# olimex_add_on.net
KiCad netlist of a schematic drawn in EAGLE
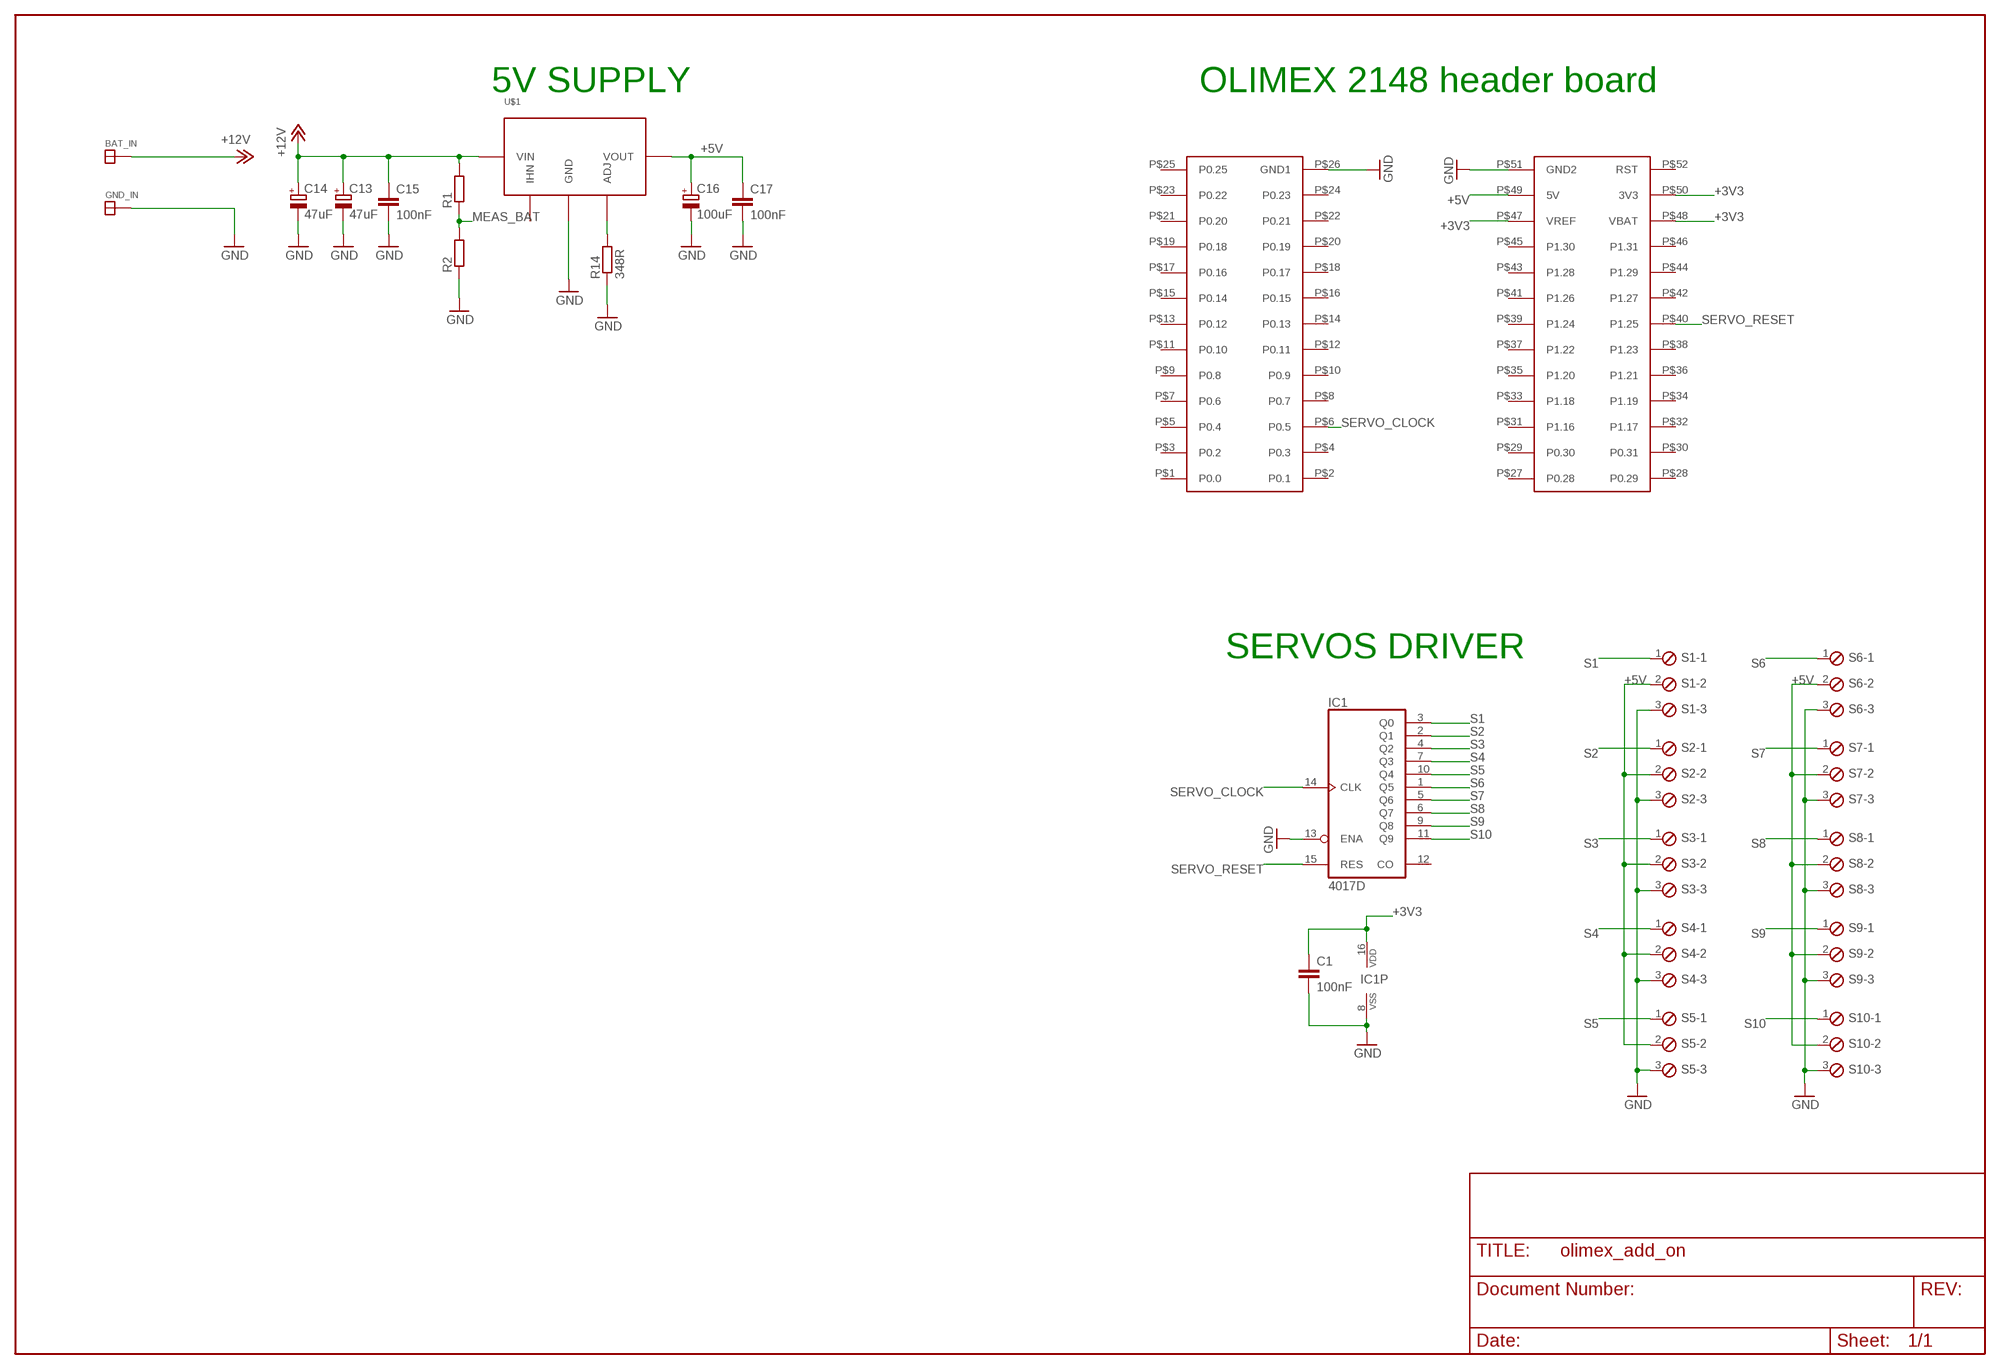
[diagram p0: schematic, sheet 1]

(export (version "E")
  (design (tool "Eeschema 10.0.6"))
  (components
    (comp (ref "BAT_IN")
      (value "SOLDER_PAD150_75")
      (footprint "eagle-import:SOLD_PAD_150_75")
      (libsource (lib "eagle-import") (part "SOLDER_PAD150_75"))
    )
    (comp (ref "C1")
      (value "100nF")
      (footprint "eagle-import:C0805K")
      (libsource (lib "eagle-import") (part "C-EUC0805K"))
    )
    (comp (ref "C13")
      (value "47uF")
      (footprint "eagle-import:SMC_D")
      (libsource (lib "eagle-import") (part "CPOL-EUSMCD"))
    )
    (comp (ref "C14")
      (value "47uF")
      (footprint "eagle-import:SMC_D")
      (libsource (lib "eagle-import") (part "CPOL-EUSMCD"))
    )
    (comp (ref "C15")
      (value "100nF")
      (footprint "eagle-import:C1206K")
      (libsource (lib "eagle-import") (part "C-EUC1206K"))
    )
    (comp (ref "C16")
      (value "100uF")
      (footprint "eagle-import:SMC_D")
      (libsource (lib "eagle-import") (part "CPOL-EUSMCD"))
    )
    (comp (ref "C17")
      (value "100nF")
      (footprint "eagle-import:C1206K")
      (libsource (lib "eagle-import") (part "C-EUC1206K"))
    )
    (comp (ref "GND_IN")
      (value "SOLDER_PAD150_75")
      (footprint "eagle-import:SOLD_PAD_150_75")
      (libsource (lib "eagle-import") (part "SOLDER_PAD150_75"))
    )
    (comp (ref "IC1")
      (value "4017D")
      (footprint "eagle-import:SO16")
      (libsource (lib "eagle-import") (part "4017D"))
    )
    (comp (ref "R1")
      (value "R-EU_R0805")
      (footprint "eagle-import:R0805")
      (libsource (lib "eagle-import") (part "R-EU_R0805"))
    )
    (comp (ref "R2")
      (value "R-EU_R0805")
      (footprint "eagle-import:R0805")
      (libsource (lib "eagle-import") (part "R-EU_R0805"))
    )
    (comp (ref "R14")
      (value "348R")
      (footprint "eagle-import:R0805")
      (libsource (lib "eagle-import") (part "R-EU_R0805"))
    )
    (comp (ref "S1")
      (value "MPT3")
      (footprint "eagle-import:3POL254")
      (libsource (lib "eagle-import") (part "MPT3"))
    )
    (comp (ref "S2")
      (value "MPT3")
      (footprint "eagle-import:3POL254")
      (libsource (lib "eagle-import") (part "MPT3"))
    )
    (comp (ref "S3")
      (value "MPT3")
      (footprint "eagle-import:3POL254")
      (libsource (lib "eagle-import") (part "MPT3"))
    )
    (comp (ref "S4")
      (value "MPT3")
      (footprint "eagle-import:3POL254")
      (libsource (lib "eagle-import") (part "MPT3"))
    )
    (comp (ref "S5")
      (value "MPT3")
      (footprint "eagle-import:3POL254")
      (libsource (lib "eagle-import") (part "MPT3"))
    )
    (comp (ref "S6")
      (value "MPT3")
      (footprint "eagle-import:3POL254")
      (libsource (lib "eagle-import") (part "MPT3"))
    )
    (comp (ref "S7")
      (value "MPT3")
      (footprint "eagle-import:3POL254")
      (libsource (lib "eagle-import") (part "MPT3"))
    )
    (comp (ref "S8")
      (value "MPT3")
      (footprint "eagle-import:3POL254")
      (libsource (lib "eagle-import") (part "MPT3"))
    )
    (comp (ref "S9")
      (value "MPT3")
      (footprint "eagle-import:3POL254")
      (libsource (lib "eagle-import") (part "MPT3"))
    )
    (comp (ref "S10")
      (value "MPT3")
      (footprint "eagle-import:3POL254")
      (libsource (lib "eagle-import") (part "MPT3"))
    )
    (comp (ref "U$1")
      (value "PTH")
      (footprint "eagle-import:PTH")
      (libsource (lib "eagle-import") (part "PTH"))
    )
    (comp (ref "U$5")
      (value "OLIMEX_2148")
      (footprint "eagle-import:OLIMEX_2148")
      (libsource (lib "eagle-import") (part "OLIMEX_2148"))
    )
  )
  (nets
    (net (code "1") (name "+12V") (class "Default")
      (node (ref "BAT_IN") (pin "P$1") (pinfunction "P$1_P$1") (pintype "bidirectional"))
      (node (ref "C13") (pin "+") (pinfunction "+_+") (pintype "passive"))
      (node (ref "C14") (pin "+") (pinfunction "+_+") (pintype "passive"))
      (node (ref "C15") (pin "1") (pinfunction "1_1") (pintype "passive"))
      (node (ref "R1") (pin "2") (pinfunction "2_2") (pintype "passive"))
      (node (ref "U$1") (pin "P$1") (pinfunction "VIN_P$1") (pintype "bidirectional"))
    )
    (net (code "2") (name "/+3V3") (class "Default")
      (node (ref "C1") (pin "1") (pinfunction "1_1") (pintype "passive"))
      (node (ref "IC1") (pin "16") (pinfunction "VDD_16") (pintype "power_in"))
      (node (ref "U$5") (pin "P$47") (pinfunction "VREF_P$47") (pintype "bidirectional"))
      (node (ref "U$5") (pin "P$48") (pinfunction "VBAT_P$48") (pintype "bidirectional"))
      (node (ref "U$5") (pin "P$50") (pinfunction "3V3_P$50") (pintype "bidirectional"))
    )
    (net (code "3") (name "/+5V") (class "Default")
      (node (ref "C16") (pin "+") (pinfunction "+_+") (pintype "passive"))
      (node (ref "C17") (pin "1") (pinfunction "1_1") (pintype "passive"))
      (node (ref "S1") (pin "2") (pinfunction "1_2") (pintype "passive"))
      (node (ref "S10") (pin "2") (pinfunction "1_2") (pintype "passive"))
      (node (ref "S2") (pin "2") (pinfunction "1_2") (pintype "passive"))
      (node (ref "S3") (pin "2") (pinfunction "1_2") (pintype "passive"))
      (node (ref "S4") (pin "2") (pinfunction "1_2") (pintype "passive"))
      (node (ref "S5") (pin "2") (pinfunction "1_2") (pintype "passive"))
      (node (ref "S6") (pin "2") (pinfunction "1_2") (pintype "passive"))
      (node (ref "S7") (pin "2") (pinfunction "1_2") (pintype "passive"))
      (node (ref "S8") (pin "2") (pinfunction "1_2") (pintype "passive"))
      (node (ref "S9") (pin "2") (pinfunction "1_2") (pintype "passive"))
      (node (ref "U$1") (pin "P$3") (pinfunction "VOUT_P$3") (pintype "bidirectional"))
      (node (ref "U$5") (pin "P$49") (pinfunction "5V_P$49") (pintype "bidirectional"))
    )
    (net (code "4") (name "/MEAS_BAT") (class "Default")
      (node (ref "R1") (pin "1") (pinfunction "1_1") (pintype "passive"))
      (node (ref "R2") (pin "2") (pinfunction "2_2") (pintype "passive"))
    )
    (net (code "5") (name "/S1") (class "Default")
      (node (ref "IC1") (pin "3") (pinfunction "Q0_3") (pintype "output"))
      (node (ref "S1") (pin "1") (pinfunction "1_1") (pintype "passive"))
    )
    (net (code "6") (name "/S2") (class "Default")
      (node (ref "IC1") (pin "2") (pinfunction "Q1_2") (pintype "output"))
      (node (ref "S2") (pin "1") (pinfunction "1_1") (pintype "passive"))
    )
    (net (code "7") (name "/S3") (class "Default")
      (node (ref "IC1") (pin "4") (pinfunction "Q2_4") (pintype "output"))
      (node (ref "S3") (pin "1") (pinfunction "1_1") (pintype "passive"))
    )
    (net (code "8") (name "/S4") (class "Default")
      (node (ref "IC1") (pin "7") (pinfunction "Q3_7") (pintype "output"))
      (node (ref "S4") (pin "1") (pinfunction "1_1") (pintype "passive"))
    )
    (net (code "9") (name "/S5") (class "Default")
      (node (ref "IC1") (pin "10") (pinfunction "Q4_10") (pintype "output"))
      (node (ref "S5") (pin "1") (pinfunction "1_1") (pintype "passive"))
    )
    (net (code "10") (name "/S6") (class "Default")
      (node (ref "IC1") (pin "1") (pinfunction "Q5_1") (pintype "output"))
      (node (ref "S6") (pin "1") (pinfunction "1_1") (pintype "passive"))
    )
    (net (code "11") (name "/S7") (class "Default")
      (node (ref "IC1") (pin "5") (pinfunction "Q6_5") (pintype "output"))
      (node (ref "S7") (pin "1") (pinfunction "1_1") (pintype "passive"))
    )
    (net (code "12") (name "/S8") (class "Default")
      (node (ref "IC1") (pin "6") (pinfunction "Q7_6") (pintype "output"))
      (node (ref "S8") (pin "1") (pinfunction "1_1") (pintype "passive"))
    )
    (net (code "13") (name "/S9") (class "Default")
      (node (ref "IC1") (pin "9") (pinfunction "Q8_9") (pintype "output"))
      (node (ref "S9") (pin "1") (pinfunction "1_1") (pintype "passive"))
    )
    (net (code "14") (name "/S10") (class "Default")
      (node (ref "IC1") (pin "11") (pinfunction "Q9_11") (pintype "output"))
      (node (ref "S10") (pin "1") (pinfunction "1_1") (pintype "passive"))
    )
    (net (code "15") (name "/SERVO_CLOCK") (class "Default")
      (node (ref "IC1") (pin "14") (pinfunction "CLK_14") (pintype "input"))
      (node (ref "U$5") (pin "P$6") (pinfunction "P0.5_P$6") (pintype "bidirectional"))
    )
    (net (code "16") (name "/SERVO_RESET") (class "Default")
      (node (ref "IC1") (pin "15") (pinfunction "RES_15") (pintype "input"))
      (node (ref "U$5") (pin "P$40") (pinfunction "P1.25_P$40") (pintype "bidirectional"))
    )
    (net (code "17") (name "GND") (class "Default")
      (node (ref "C1") (pin "2") (pinfunction "2_2") (pintype "passive"))
      (node (ref "C13") (pin "-") (pinfunction "-_-") (pintype "passive"))
      (node (ref "C14") (pin "-") (pinfunction "-_-") (pintype "passive"))
      (node (ref "C15") (pin "2") (pinfunction "2_2") (pintype "passive"))
      (node (ref "C16") (pin "-") (pinfunction "-_-") (pintype "passive"))
      (node (ref "C17") (pin "2") (pinfunction "2_2") (pintype "passive"))
      (node (ref "GND_IN") (pin "P$1") (pinfunction "P$1_P$1") (pintype "bidirectional"))
      (node (ref "IC1") (pin "13") (pinfunction "ENA_13") (pintype "input"))
      (node (ref "IC1") (pin "8") (pinfunction "VSS_8") (pintype "power_in"))
      (node (ref "R14") (pin "1") (pinfunction "1_1") (pintype "passive"))
      (node (ref "R2") (pin "1") (pinfunction "1_1") (pintype "passive"))
      (node (ref "S1") (pin "3") (pinfunction "1_3") (pintype "passive"))
      (node (ref "S10") (pin "3") (pinfunction "1_3") (pintype "passive"))
      (node (ref "S2") (pin "3") (pinfunction "1_3") (pintype "passive"))
      (node (ref "S3") (pin "3") (pinfunction "1_3") (pintype "passive"))
      (node (ref "S4") (pin "3") (pinfunction "1_3") (pintype "passive"))
      (node (ref "S5") (pin "3") (pinfunction "1_3") (pintype "passive"))
      (node (ref "S6") (pin "3") (pinfunction "1_3") (pintype "passive"))
      (node (ref "S7") (pin "3") (pinfunction "1_3") (pintype "passive"))
      (node (ref "S8") (pin "3") (pinfunction "1_3") (pintype "passive"))
      (node (ref "S9") (pin "3") (pinfunction "1_3") (pintype "passive"))
      (node (ref "U$1") (pin "P$2") (pinfunction "GND_P$2") (pintype "bidirectional"))
      (node (ref "U$5") (pin "P$26") (pinfunction "GND1_P$26") (pintype "bidirectional"))
      (node (ref "U$5") (pin "P$51") (pinfunction "GND2_P$51") (pintype "bidirectional"))
    )
    (net (code "18") (name "Net-(U$1-ADJ)") (class "Default")
      (node (ref "R14") (pin "2") (pinfunction "2_2") (pintype "passive"))
      (node (ref "U$1") (pin "P$4") (pinfunction "ADJ_P$4") (pintype "bidirectional"))
    )
    (net (code "19") (name "unconnected-(IC1A-CO-Pad12)") (class "Default")
      (node (ref "IC1") (pin "12") (pinfunction "CO_12") (pintype "output"))
    )
    (net (code "20") (name "unconnected-(U$1-IHN-PadP$5)") (class "Default")
      (node (ref "U$1") (pin "P$5") (pinfunction "IHN_P$5") (pintype "bidirectional"))
    )
    (net (code "21") (name "unconnected-(U$5-P0.0-PadP$1)") (class "Default")
      (node (ref "U$5") (pin "P$1") (pinfunction "P0.0_P$1") (pintype "bidirectional"))
    )
    (net (code "22") (name "unconnected-(U$5-P0.1-PadP$2)") (class "Default")
      (node (ref "U$5") (pin "P$2") (pinfunction "P0.1_P$2") (pintype "bidirectional"))
    )
    (net (code "23") (name "unconnected-(U$5-P0.2-PadP$3)") (class "Default")
      (node (ref "U$5") (pin "P$3") (pinfunction "P0.2_P$3") (pintype "bidirectional"))
    )
    (net (code "24") (name "unconnected-(U$5-P0.3-PadP$4)") (class "Default")
      (node (ref "U$5") (pin "P$4") (pinfunction "P0.3_P$4") (pintype "bidirectional"))
    )
    (net (code "25") (name "unconnected-(U$5-P0.4-PadP$5)") (class "Default")
      (node (ref "U$5") (pin "P$5") (pinfunction "P0.4_P$5") (pintype "bidirectional"))
    )
    (net (code "26") (name "unconnected-(U$5-P0.6-PadP$7)") (class "Default")
      (node (ref "U$5") (pin "P$7") (pinfunction "P0.6_P$7") (pintype "bidirectional"))
    )
    (net (code "27") (name "unconnected-(U$5-P0.7-PadP$8)") (class "Default")
      (node (ref "U$5") (pin "P$8") (pinfunction "P0.7_P$8") (pintype "bidirectional"))
    )
    (net (code "28") (name "unconnected-(U$5-P0.8-PadP$9)") (class "Default")
      (node (ref "U$5") (pin "P$9") (pinfunction "P0.8_P$9") (pintype "bidirectional"))
    )
    (net (code "29") (name "unconnected-(U$5-P0.9-PadP$10)") (class "Default")
      (node (ref "U$5") (pin "P$10") (pinfunction "P0.9_P$10") (pintype "bidirectional"))
    )
    (net (code "30") (name "unconnected-(U$5-P0.10-PadP$11)") (class "Default")
      (node (ref "U$5") (pin "P$11") (pinfunction "P0.10_P$11") (pintype "bidirectional"))
    )
    (net (code "31") (name "unconnected-(U$5-P0.11-PadP$12)") (class "Default")
      (node (ref "U$5") (pin "P$12") (pinfunction "P0.11_P$12") (pintype "bidirectional"))
    )
    (net (code "32") (name "unconnected-(U$5-P0.12-PadP$13)") (class "Default")
      (node (ref "U$5") (pin "P$13") (pinfunction "P0.12_P$13") (pintype "bidirectional"))
    )
    (net (code "33") (name "unconnected-(U$5-P0.13-PadP$14)") (class "Default")
      (node (ref "U$5") (pin "P$14") (pinfunction "P0.13_P$14") (pintype "bidirectional"))
    )
    (net (code "34") (name "unconnected-(U$5-P0.14-PadP$15)") (class "Default")
      (node (ref "U$5") (pin "P$15") (pinfunction "P0.14_P$15") (pintype "bidirectional"))
    )
    (net (code "35") (name "unconnected-(U$5-P0.15-PadP$16)") (class "Default")
      (node (ref "U$5") (pin "P$16") (pinfunction "P0.15_P$16") (pintype "bidirectional"))
    )
    (net (code "36") (name "unconnected-(U$5-P0.16-PadP$17)") (class "Default")
      (node (ref "U$5") (pin "P$17") (pinfunction "P0.16_P$17") (pintype "bidirectional"))
    )
    (net (code "37") (name "unconnected-(U$5-P0.17-PadP$18)") (class "Default")
      (node (ref "U$5") (pin "P$18") (pinfunction "P0.17_P$18") (pintype "bidirectional"))
    )
    (net (code "38") (name "unconnected-(U$5-P0.18-PadP$19)") (class "Default")
      (node (ref "U$5") (pin "P$19") (pinfunction "P0.18_P$19") (pintype "bidirectional"))
    )
    (net (code "39") (name "unconnected-(U$5-P0.19-PadP$20)") (class "Default")
      (node (ref "U$5") (pin "P$20") (pinfunction "P0.19_P$20") (pintype "bidirectional"))
    )
    (net (code "40") (name "unconnected-(U$5-P0.20-PadP$21)") (class "Default")
      (node (ref "U$5") (pin "P$21") (pinfunction "P0.20_P$21") (pintype "bidirectional"))
    )
    (net (code "41") (name "unconnected-(U$5-P0.21-PadP$22)") (class "Default")
      (node (ref "U$5") (pin "P$22") (pinfunction "P0.21_P$22") (pintype "bidirectional"))
    )
    (net (code "42") (name "unconnected-(U$5-P0.22-PadP$23)") (class "Default")
      (node (ref "U$5") (pin "P$23") (pinfunction "P0.22_P$23") (pintype "bidirectional"))
    )
    (net (code "43") (name "unconnected-(U$5-P0.23-PadP$24)") (class "Default")
      (node (ref "U$5") (pin "P$24") (pinfunction "P0.23_P$24") (pintype "bidirectional"))
    )
    (net (code "44") (name "unconnected-(U$5-P0.25-PadP$25)") (class "Default")
      (node (ref "U$5") (pin "P$25") (pinfunction "P0.25_P$25") (pintype "bidirectional"))
    )
    (net (code "45") (name "unconnected-(U$5-P0.28-PadP$27)") (class "Default")
      (node (ref "U$5") (pin "P$27") (pinfunction "P0.28_P$27") (pintype "bidirectional"))
    )
    (net (code "46") (name "unconnected-(U$5-P0.29-PadP$28)") (class "Default")
      (node (ref "U$5") (pin "P$28") (pinfunction "P0.29_P$28") (pintype "bidirectional"))
    )
    (net (code "47") (name "unconnected-(U$5-P0.30-PadP$29)") (class "Default")
      (node (ref "U$5") (pin "P$29") (pinfunction "P0.30_P$29") (pintype "bidirectional"))
    )
    (net (code "48") (name "unconnected-(U$5-P0.31-PadP$30)") (class "Default")
      (node (ref "U$5") (pin "P$30") (pinfunction "P0.31_P$30") (pintype "bidirectional"))
    )
    (net (code "49") (name "unconnected-(U$5-P1.16-PadP$31)") (class "Default")
      (node (ref "U$5") (pin "P$31") (pinfunction "P1.16_P$31") (pintype "bidirectional"))
    )
    (net (code "50") (name "unconnected-(U$5-P1.17-PadP$32)") (class "Default")
      (node (ref "U$5") (pin "P$32") (pinfunction "P1.17_P$32") (pintype "bidirectional"))
    )
    (net (code "51") (name "unconnected-(U$5-P1.18-PadP$33)") (class "Default")
      (node (ref "U$5") (pin "P$33") (pinfunction "P1.18_P$33") (pintype "bidirectional"))
    )
    (net (code "52") (name "unconnected-(U$5-P1.19-PadP$34)") (class "Default")
      (node (ref "U$5") (pin "P$34") (pinfunction "P1.19_P$34") (pintype "bidirectional"))
    )
    (net (code "53") (name "unconnected-(U$5-P1.20-PadP$35)") (class "Default")
      (node (ref "U$5") (pin "P$35") (pinfunction "P1.20_P$35") (pintype "bidirectional"))
    )
    (net (code "54") (name "unconnected-(U$5-P1.21-PadP$36)") (class "Default")
      (node (ref "U$5") (pin "P$36") (pinfunction "P1.21_P$36") (pintype "bidirectional"))
    )
    (net (code "55") (name "unconnected-(U$5-P1.22-PadP$37)") (class "Default")
      (node (ref "U$5") (pin "P$37") (pinfunction "P1.22_P$37") (pintype "bidirectional"))
    )
    (net (code "56") (name "unconnected-(U$5-P1.23-PadP$38)") (class "Default")
      (node (ref "U$5") (pin "P$38") (pinfunction "P1.23_P$38") (pintype "bidirectional"))
    )
    (net (code "57") (name "unconnected-(U$5-P1.24-PadP$39)") (class "Default")
      (node (ref "U$5") (pin "P$39") (pinfunction "P1.24_P$39") (pintype "bidirectional"))
    )
    (net (code "58") (name "unconnected-(U$5-P1.26-PadP$41)") (class "Default")
      (node (ref "U$5") (pin "P$41") (pinfunction "P1.26_P$41") (pintype "bidirectional"))
    )
    (net (code "59") (name "unconnected-(U$5-P1.27-PadP$42)") (class "Default")
      (node (ref "U$5") (pin "P$42") (pinfunction "P1.27_P$42") (pintype "bidirectional"))
    )
    (net (code "60") (name "unconnected-(U$5-P1.28-PadP$43)") (class "Default")
      (node (ref "U$5") (pin "P$43") (pinfunction "P1.28_P$43") (pintype "bidirectional"))
    )
    (net (code "61") (name "unconnected-(U$5-P1.29-PadP$44)") (class "Default")
      (node (ref "U$5") (pin "P$44") (pinfunction "P1.29_P$44") (pintype "bidirectional"))
    )
    (net (code "62") (name "unconnected-(U$5-P1.30-PadP$45)") (class "Default")
      (node (ref "U$5") (pin "P$45") (pinfunction "P1.30_P$45") (pintype "bidirectional"))
    )
    (net (code "63") (name "unconnected-(U$5-P1.31-PadP$46)") (class "Default")
      (node (ref "U$5") (pin "P$46") (pinfunction "P1.31_P$46") (pintype "bidirectional"))
    )
    (net (code "64") (name "unconnected-(U$5-RST-PadP$52)") (class "Default")
      (node (ref "U$5") (pin "P$52") (pinfunction "RST_P$52") (pintype "bidirectional"))
    )
  )
)
